# ultrasonic_detector.net
KiCad netlist of a schematic drawn in EAGLE
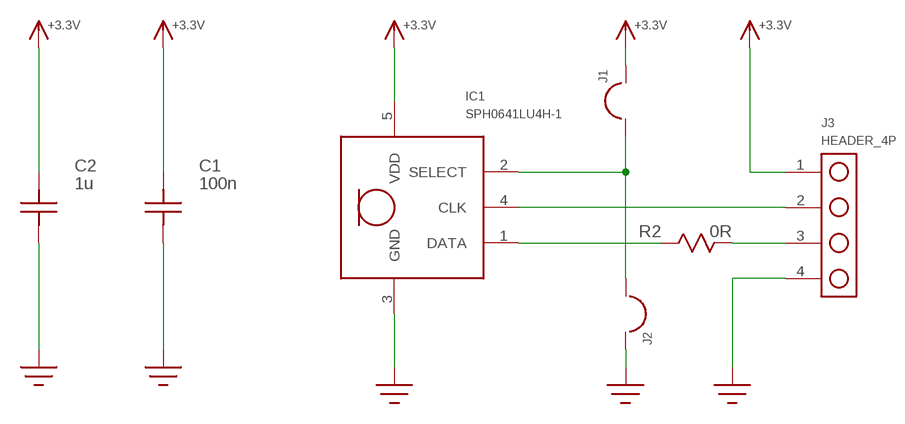
[diagram p0: schematic, sheet 1]

(export (version "E")
  (design (tool "Eeschema 10.0.6"))
  (components
    (comp (ref "C1")
      (value "100n")
      (footprint "eagle-import:C0603")
      (libsource (lib "eagle-import") (part "C0603"))
    )
    (comp (ref "C2")
      (value "1u")
      (footprint "eagle-import:C0603")
      (libsource (lib "eagle-import") (part "C0603"))
    )
    (comp (ref "IC1")
      (value "SPH0641LU4H-1")
      (footprint "eagle-import:SPH0641LU4H-1")
      (libsource (lib "eagle-import") (part "SPH0641LU4H-1"))
    )
    (comp (ref "J1")
      (value "SOLDER_BRIDGE")
      (footprint "eagle-import:SOLDER_BRIDGE")
      (libsource (lib "eagle-import") (part "SOLDER_BRIDGE"))
    )
    (comp (ref "J2")
      (value "SOLDER_BRIDGE")
      (footprint "eagle-import:SOLDER_BRIDGE")
      (libsource (lib "eagle-import") (part "SOLDER_BRIDGE"))
    )
    (comp (ref "J3")
      (value "HEADER_4P")
      (footprint "eagle-import:HEADER_4P")
      (libsource (lib "eagle-import") (part "HEADER_4P"))
    )
    (comp (ref "R2")
      (value "0R")
      (footprint "eagle-import:R0603")
      (libsource (lib "eagle-import") (part "R0603"))
    )
  )
  (nets
    (net (code "1") (name "+3.3V") (class "Default")
      (node (ref "C1") (pin "P$2") (pinfunction "P$2_P$2") (pintype "bidirectional"))
      (node (ref "C2") (pin "P$2") (pinfunction "P$2_P$2") (pintype "bidirectional"))
      (node (ref "IC1") (pin "5") (pinfunction "VDD_5") (pintype "bidirectional"))
      (node (ref "J1") (pin "2@1") (pinfunction "P$2_2@1") (pintype "bidirectional"))
      (node (ref "J1") (pin "2@2") (pinfunction "P$2_2@2") (pintype "bidirectional"))
      (node (ref "J1") (pin "2@3") (pinfunction "P$2_2@3") (pintype "bidirectional"))
      (node (ref "J3") (pin "1") (pinfunction "1_1") (pintype "bidirectional"))
    )
    (net (code "2") (name "GND") (class "Default")
      (node (ref "C1") (pin "P$1") (pinfunction "P$1_P$1") (pintype "bidirectional"))
      (node (ref "C2") (pin "P$1") (pinfunction "P$1_P$1") (pintype "bidirectional"))
      (node (ref "IC1") (pin "3") (pinfunction "GND_3") (pintype "bidirectional"))
      (node (ref "J2") (pin "2@1") (pinfunction "P$2_2@1") (pintype "bidirectional"))
      (node (ref "J2") (pin "2@2") (pinfunction "P$2_2@2") (pintype "bidirectional"))
      (node (ref "J2") (pin "2@3") (pinfunction "P$2_2@3") (pintype "bidirectional"))
      (node (ref "J3") (pin "4") (pinfunction "4_4") (pintype "bidirectional"))
    )
    (net (code "3") (name "Net-(IC1-CLK)") (class "Default")
      (node (ref "IC1") (pin "4") (pinfunction "CLK_4") (pintype "bidirectional"))
      (node (ref "J3") (pin "2") (pinfunction "2_2") (pintype "bidirectional"))
    )
    (net (code "4") (name "Net-(IC1-DATA)") (class "Default")
      (node (ref "IC1") (pin "1") (pinfunction "DATA_1") (pintype "bidirectional"))
      (node (ref "R2") (pin "P$1") (pinfunction "P$3_P$1") (pintype "bidirectional"))
    )
    (net (code "5") (name "Net-(IC1-SELECT)") (class "Default")
      (node (ref "IC1") (pin "2") (pinfunction "SELECT_2") (pintype "bidirectional"))
      (node (ref "J1") (pin "1") (pinfunction "P$1_1") (pintype "bidirectional"))
      (node (ref "J2") (pin "1") (pinfunction "P$1_1") (pintype "bidirectional"))
    )
    (net (code "6") (name "Net-(R2-P$4)") (class "Default")
      (node (ref "J3") (pin "3") (pinfunction "3_3") (pintype "bidirectional"))
      (node (ref "R2") (pin "P$2") (pinfunction "P$4_P$2") (pintype "bidirectional"))
    )
  )
)
